# ProPrj_IR-Sensor-I2C_2025-01-15_1.net
KiCad netlist of a schematic drawn in EasyEDA Pro
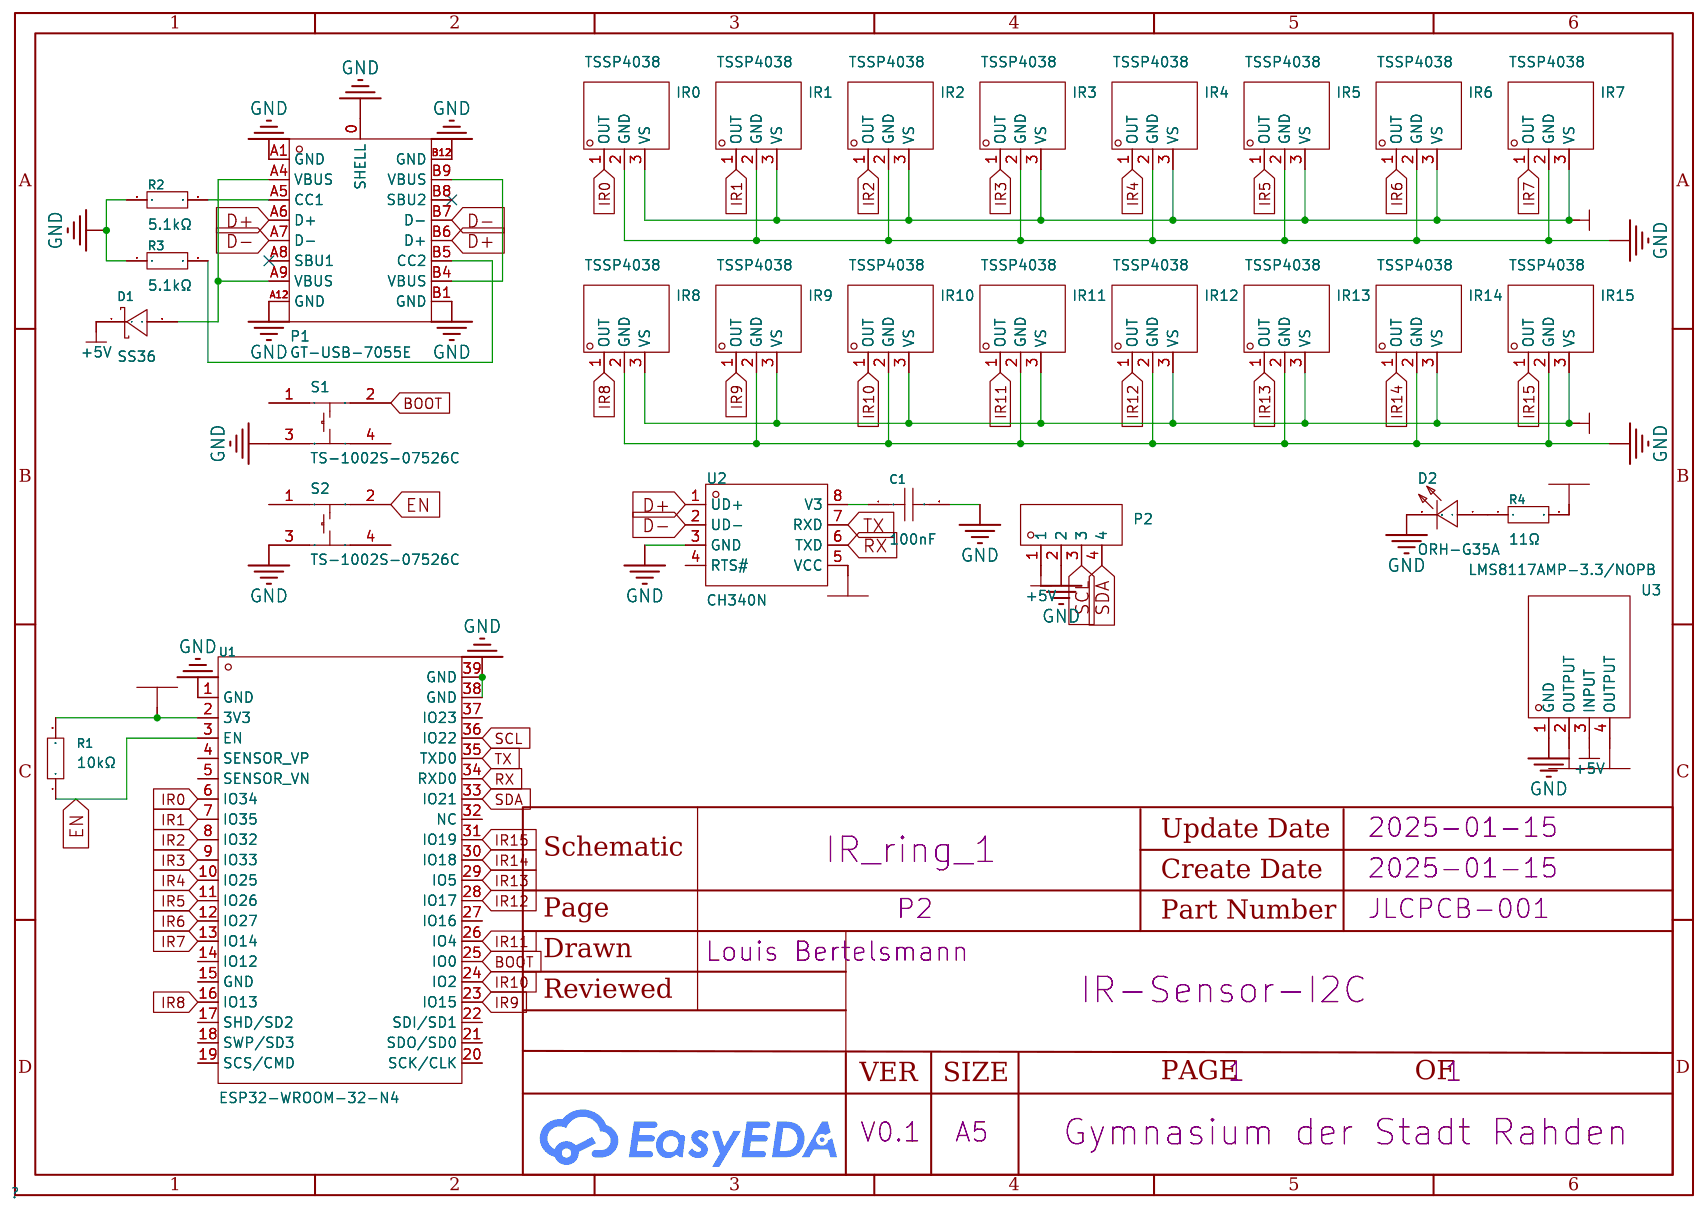
[diagram p0: schematic sheet]

(export (version "E")
  (design (tool "Eeschema 10.0.6"))
  (components
    (comp (ref "C1")
      (value "100nF")
      (footprint "easyedapro:C0603")
      (fields
        (field (name "Manufacturer Part") "CC0603KRX7R9BB104")
        (field (name "Manufacturer") "YAGEO(国巨)")
      )
      (libsource (lib "easyedapro") (part "CC0603KRX7R9BB104"))
    )
    (comp (ref "D1")
      (value "SS36")
      (footprint "easyedapro:SMA_L4.4-W2.8-LS5.4-RD")
      (description "Forward Voltage (Vf@If):700mV@3A Reverse Voltage (Vr):60V Average Rectified Current (Io):3A")
      (fields (field (name "Manufacturer") "晶导微电子"))
      (libsource (lib "easyedapro") (part "SS36_C116712"))
    )
    (comp (ref "D2")
      (value "ORH-G35A")
      (footprint "easyedapro:LED0805-R-RD")
      (fields (field (name "Manufacturer") "Orient(奥伦德)"))
      (libsource (lib "easyedapro") (part "ORH-G35A"))
    )
    (comp (ref "IR0")
      (value "TSSP4038")
      (footprint "easyedapro:SENSOR-TH_TSSP40X")
      (fields (field (name "Manufacturer") "VISHAY(威世)"))
      (libsource (lib "easyedapro") (part "TSSP4038"))
    )
    (comp (ref "IR1")
      (value "TSSP4038")
      (footprint "easyedapro:SENSOR-TH_TSSP40X")
      (fields (field (name "Manufacturer") "VISHAY(威世)"))
      (libsource (lib "easyedapro") (part "TSSP4038"))
    )
    (comp (ref "IR2")
      (value "TSSP4038")
      (footprint "easyedapro:SENSOR-TH_TSSP40X")
      (fields (field (name "Manufacturer") "VISHAY(威世)"))
      (libsource (lib "easyedapro") (part "TSSP4038"))
    )
    (comp (ref "IR3")
      (value "TSSP4038")
      (footprint "easyedapro:SENSOR-TH_TSSP40X")
      (fields (field (name "Manufacturer") "VISHAY(威世)"))
      (libsource (lib "easyedapro") (part "TSSP4038"))
    )
    (comp (ref "IR4")
      (value "TSSP4038")
      (footprint "easyedapro:SENSOR-TH_TSSP40X")
      (fields (field (name "Manufacturer") "VISHAY(威世)"))
      (libsource (lib "easyedapro") (part "TSSP4038"))
    )
    (comp (ref "IR5")
      (value "TSSP4038")
      (footprint "easyedapro:SENSOR-TH_TSSP40X")
      (fields (field (name "Manufacturer") "VISHAY(威世)"))
      (libsource (lib "easyedapro") (part "TSSP4038"))
    )
    (comp (ref "IR6")
      (value "TSSP4038")
      (footprint "easyedapro:SENSOR-TH_TSSP40X")
      (fields (field (name "Manufacturer") "VISHAY(威世)"))
      (libsource (lib "easyedapro") (part "TSSP4038"))
    )
    (comp (ref "IR7")
      (value "TSSP4038")
      (footprint "easyedapro:SENSOR-TH_TSSP40X")
      (fields (field (name "Manufacturer") "VISHAY(威世)"))
      (libsource (lib "easyedapro") (part "TSSP4038"))
    )
    (comp (ref "IR8")
      (value "TSSP4038")
      (footprint "easyedapro:SENSOR-TH_TSSP40X")
      (fields (field (name "Manufacturer") "VISHAY(威世)"))
      (libsource (lib "easyedapro") (part "TSSP4038"))
    )
    (comp (ref "IR9")
      (value "TSSP4038")
      (footprint "easyedapro:SENSOR-TH_TSSP40X")
      (fields (field (name "Manufacturer") "VISHAY(威世)"))
      (libsource (lib "easyedapro") (part "TSSP4038"))
    )
    (comp (ref "IR10")
      (value "TSSP4038")
      (footprint "easyedapro:SENSOR-TH_TSSP40X")
      (fields (field (name "Manufacturer") "VISHAY(威世)"))
      (libsource (lib "easyedapro") (part "TSSP4038"))
    )
    (comp (ref "IR11")
      (value "TSSP4038")
      (footprint "easyedapro:SENSOR-TH_TSSP40X")
      (fields (field (name "Manufacturer") "VISHAY(威世)"))
      (libsource (lib "easyedapro") (part "TSSP4038"))
    )
    (comp (ref "IR12")
      (value "TSSP4038")
      (footprint "easyedapro:SENSOR-TH_TSSP40X")
      (fields (field (name "Manufacturer") "VISHAY(威世)"))
      (libsource (lib "easyedapro") (part "TSSP4038"))
    )
    (comp (ref "IR13")
      (value "TSSP4038")
      (footprint "easyedapro:SENSOR-TH_TSSP40X")
      (fields (field (name "Manufacturer") "VISHAY(威世)"))
      (libsource (lib "easyedapro") (part "TSSP4038"))
    )
    (comp (ref "IR14")
      (value "TSSP4038")
      (footprint "easyedapro:SENSOR-TH_TSSP40X")
      (fields (field (name "Manufacturer") "VISHAY(威世)"))
      (libsource (lib "easyedapro") (part "TSSP4038"))
    )
    (comp (ref "IR15")
      (value "TSSP4038")
      (footprint "easyedapro:SENSOR-TH_TSSP40X")
      (fields (field (name "Manufacturer") "VISHAY(威世)"))
      (libsource (lib "easyedapro") (part "TSSP4038"))
    )
    (comp (ref "P1")
      (value "GT-USB-7055E")
      (footprint "easyedapro:USB-C-SMD_GT-USB-7055E")
      (fields (field (name "Manufacturer") "G-Switch(品赞)"))
      (libsource (lib "easyedapro") (part "GT-USB-7055E"))
    )
    (comp (ref "P2")
      (value "DZ254S-11-04-48")
      (footprint "easyedapro:HDR-SMD_4P-P2.54-V-M-LS4.8_R2")
      (fields (field (name "Manufacturer") "DEALON(德艺隆)"))
      (libsource (lib "easyedapro") (part "DZ254S-11-04-48"))
    )
    (comp (ref "R1")
      (value "10kΩ")
      (footprint "easyedapro:R0603")
      (fields
        (field (name "Manufacturer Part") "0603WAF1002T5E")
        (field (name "Manufacturer") "UNI-ROYAL(厚声)")
      )
      (libsource (lib "easyedapro") (part "0603WAF1002T5E"))
    )
    (comp (ref "R2")
      (value "5.1kΩ")
      (footprint "easyedapro:R0603")
      (fields
        (field (name "Manufacturer Part") "0603WAF5101T5E")
        (field (name "Manufacturer") "UNI-ROYAL(厚声)")
      )
      (libsource (lib "easyedapro") (part "0603WAF5101T5E"))
    )
    (comp (ref "R3")
      (value "5.1kΩ")
      (footprint "easyedapro:R0603")
      (fields
        (field (name "Manufacturer Part") "0603WAF5101T5E")
        (field (name "Manufacturer") "UNI-ROYAL(厚声)")
      )
      (libsource (lib "easyedapro") (part "0603WAF5101T5E"))
    )
    (comp (ref "R4")
      (value "11Ω")
      (footprint "easyedapro:R0603")
      (fields
        (field (name "Manufacturer Part") "0603WAF110JT5E")
        (field (name "Manufacturer") "UNI-ROYAL(厚声)")
      )
      (libsource (lib "easyedapro") (part "0603WAF110JT5E"))
    )
    (comp (ref "S1")
      (value "TS-1002S-07526C")
      (footprint "easyedapro:SW-SMD_4P-L6.0-W6.0-P4.50-LS9.0-2")
      (fields (field (name "Manufacturer") "XUNPU(讯普)"))
      (libsource (lib "easyedapro") (part "TS-1002S-07526C"))
    )
    (comp (ref "S2")
      (value "TS-1002S-07526C")
      (footprint "easyedapro:SW-SMD_4P-L6.0-W6.0-P4.50-LS9.0-2")
      (fields (field (name "Manufacturer") "XUNPU(讯普)"))
      (libsource (lib "easyedapro") (part "TS-1002S-07526C"))
    )
    (comp (ref "U1")
      (value "ESP32-WROOM-32-N4")
      (footprint "easyedapro:WIFIM-SMD_ESP32-WROOM-32-N4")
      (fields (field (name "Manufacturer") "ESPRESSIF(乐鑫)"))
      (libsource (lib "easyedapro") (part "ESP32-WROOM-32"))
    )
    (comp (ref "U2")
      (value "CH340N")
      (footprint "easyedapro:SOP-8_L4.9-W3.9-P1.27-LS6.0-BL")
      (fields (field (name "Manufacturer") "WCH(南京沁恒)"))
      (libsource (lib "easyedapro") (part "CH340N_C2977777"))
    )
    (comp (ref "U3")
      (value "LMS8117AMP-3.3/NOPB")
      (footprint "easyedapro:SOT-223_L6.5-W3.5-P2.30-LS7.0-BR")
      (fields (field (name "Manufacturer") "TI(德州仪器)"))
      (libsource (lib "easyedapro") (part "LMS8117AMP-3.3/NOPB"))
    )
  )
  (nets
    (net (code "1") (name "+5V") (class "Default")
      (node (ref "D1") (pin "1") (pinfunction "K_1") (pintype "input"))
      (node (ref "P2") (pin "1") (pinfunction "1_1") (pintype "unspecified"))
      (node (ref "U3") (pin "3") (pinfunction "INPUT_3") (pintype "unspecified"))
    )
    (net (code "2") (name "3V3") (class "Default")
      (node (ref "IR0") (pin "3") (pinfunction "VS_3") (pintype "input"))
      (node (ref "IR1") (pin "3") (pinfunction "VS_3") (pintype "input"))
      (node (ref "IR10") (pin "3") (pinfunction "VS_3") (pintype "input"))
      (node (ref "IR11") (pin "3") (pinfunction "VS_3") (pintype "input"))
      (node (ref "IR12") (pin "3") (pinfunction "VS_3") (pintype "input"))
      (node (ref "IR13") (pin "3") (pinfunction "VS_3") (pintype "input"))
      (node (ref "IR14") (pin "3") (pinfunction "VS_3") (pintype "input"))
      (node (ref "IR15") (pin "3") (pinfunction "VS_3") (pintype "input"))
      (node (ref "IR2") (pin "3") (pinfunction "VS_3") (pintype "input"))
      (node (ref "IR3") (pin "3") (pinfunction "VS_3") (pintype "input"))
      (node (ref "IR4") (pin "3") (pinfunction "VS_3") (pintype "input"))
      (node (ref "IR5") (pin "3") (pinfunction "VS_3") (pintype "input"))
      (node (ref "IR6") (pin "3") (pinfunction "VS_3") (pintype "input"))
      (node (ref "IR7") (pin "3") (pinfunction "VS_3") (pintype "input"))
      (node (ref "IR8") (pin "3") (pinfunction "VS_3") (pintype "input"))
      (node (ref "IR9") (pin "3") (pinfunction "VS_3") (pintype "input"))
      (node (ref "R1") (pin "2") (pinfunction "2_2") (pintype "input"))
      (node (ref "R4") (pin "2") (pinfunction "2_2") (pintype "input"))
      (node (ref "U1") (pin "2") (pinfunction "3V3_2") (pintype "input"))
      (node (ref "U2") (pin "5") (pinfunction "VCC_5") (pintype "unspecified"))
      (node (ref "U3") (pin "2") (pinfunction "OUTPUT_2") (pintype "unspecified"))
      (node (ref "U3") (pin "4") (pinfunction "OUTPUT_4") (pintype "unspecified"))
    )
    (net (code "3") (name "BOOT") (class "Default")
      (node (ref "S1") (pin "2") (pinfunction "2_2") (pintype "input"))
      (node (ref "U1") (pin "25") (pinfunction "IO0_25") (pintype "input"))
    )
    (net (code "4") (name "D+") (class "Default")
      (node (ref "P1") (pin "A6") (pinfunction "D+_A6") (pintype "unspecified"))
      (node (ref "P1") (pin "B6") (pinfunction "D+_B6") (pintype "unspecified"))
      (node (ref "U2") (pin "1") (pinfunction "UD+_1") (pintype "unspecified"))
    )
    (net (code "5") (name "D-") (class "Default")
      (node (ref "P1") (pin "A7") (pinfunction "D-_A7") (pintype "unspecified"))
      (node (ref "P1") (pin "B7") (pinfunction "D-_B7") (pintype "unspecified"))
      (node (ref "U2") (pin "2") (pinfunction "UD-_2") (pintype "unspecified"))
    )
    (net (code "6") (name "EN") (class "Default")
      (node (ref "R1") (pin "1") (pinfunction "1_1") (pintype "input"))
      (node (ref "S2") (pin "2") (pinfunction "2_2") (pintype "input"))
      (node (ref "U1") (pin "3") (pinfunction "EN_3") (pintype "input"))
    )
    (net (code "7") (name "GND") (class "Default")
      (node (ref "C1") (pin "2") (pinfunction "2_2") (pintype "input"))
      (node (ref "D2") (pin "2") (pinfunction "C_2") (pintype "unspecified"))
      (node (ref "IR0") (pin "2") (pinfunction "GND_2") (pintype "input"))
      (node (ref "IR1") (pin "2") (pinfunction "GND_2") (pintype "input"))
      (node (ref "IR10") (pin "2") (pinfunction "GND_2") (pintype "input"))
      (node (ref "IR11") (pin "2") (pinfunction "GND_2") (pintype "input"))
      (node (ref "IR12") (pin "2") (pinfunction "GND_2") (pintype "input"))
      (node (ref "IR13") (pin "2") (pinfunction "GND_2") (pintype "input"))
      (node (ref "IR14") (pin "2") (pinfunction "GND_2") (pintype "input"))
      (node (ref "IR15") (pin "2") (pinfunction "GND_2") (pintype "input"))
      (node (ref "IR2") (pin "2") (pinfunction "GND_2") (pintype "input"))
      (node (ref "IR3") (pin "2") (pinfunction "GND_2") (pintype "input"))
      (node (ref "IR4") (pin "2") (pinfunction "GND_2") (pintype "input"))
      (node (ref "IR5") (pin "2") (pinfunction "GND_2") (pintype "input"))
      (node (ref "IR6") (pin "2") (pinfunction "GND_2") (pintype "input"))
      (node (ref "IR7") (pin "2") (pinfunction "GND_2") (pintype "input"))
      (node (ref "IR8") (pin "2") (pinfunction "GND_2") (pintype "input"))
      (node (ref "IR9") (pin "2") (pinfunction "GND_2") (pintype "input"))
      (node (ref "P1") (pin "0") (pinfunction "SHELL_0") (pintype "unspecified"))
      (node (ref "P1") (pin "A1") (pinfunction "GND_A1") (pintype "unspecified"))
      (node (ref "P1") (pin "A12") (pinfunction "GND_A12") (pintype "unspecified"))
      (node (ref "P1") (pin "B1") (pinfunction "GND_B1") (pintype "unspecified"))
      (node (ref "P1") (pin "B12") (pinfunction "GND_B12") (pintype "unspecified"))
      (node (ref "P2") (pin "2") (pinfunction "2_2") (pintype "unspecified"))
      (node (ref "R2") (pin "1") (pinfunction "1_1") (pintype "input"))
      (node (ref "R3") (pin "1") (pinfunction "1_1") (pintype "input"))
      (node (ref "S1") (pin "3") (pinfunction "3_3") (pintype "input"))
      (node (ref "S2") (pin "3") (pinfunction "3_3") (pintype "input"))
      (node (ref "U1") (pin "1") (pinfunction "GND_1") (pintype "input"))
      (node (ref "U1") (pin "38") (pinfunction "GND_38") (pintype "input"))
      (node (ref "U1") (pin "39") (pinfunction "GND_39") (pintype "input"))
      (node (ref "U2") (pin "3") (pinfunction "GND_3") (pintype "unspecified"))
      (node (ref "U3") (pin "1") (pinfunction "GND_1") (pintype "unspecified"))
    )
    (net (code "8") (name "IR0") (class "Default")
      (node (ref "IR0") (pin "1") (pinfunction "OUT_1") (pintype "input"))
      (node (ref "U1") (pin "6") (pinfunction "IO34_6") (pintype "input"))
    )
    (net (code "9") (name "IR1") (class "Default")
      (node (ref "IR1") (pin "1") (pinfunction "OUT_1") (pintype "input"))
      (node (ref "U1") (pin "7") (pinfunction "IO35_7") (pintype "input"))
    )
    (net (code "10") (name "IR2") (class "Default")
      (node (ref "IR2") (pin "1") (pinfunction "OUT_1") (pintype "input"))
      (node (ref "U1") (pin "8") (pinfunction "IO32_8") (pintype "input"))
    )
    (net (code "11") (name "IR3") (class "Default")
      (node (ref "IR3") (pin "1") (pinfunction "OUT_1") (pintype "input"))
      (node (ref "U1") (pin "9") (pinfunction "IO33_9") (pintype "input"))
    )
    (net (code "12") (name "IR4") (class "Default")
      (node (ref "IR4") (pin "1") (pinfunction "OUT_1") (pintype "input"))
      (node (ref "U1") (pin "10") (pinfunction "IO25_10") (pintype "input"))
    )
    (net (code "13") (name "IR5") (class "Default")
      (node (ref "IR5") (pin "1") (pinfunction "OUT_1") (pintype "input"))
      (node (ref "U1") (pin "11") (pinfunction "IO26_11") (pintype "input"))
    )
    (net (code "14") (name "IR6") (class "Default")
      (node (ref "IR6") (pin "1") (pinfunction "OUT_1") (pintype "input"))
      (node (ref "U1") (pin "12") (pinfunction "IO27_12") (pintype "input"))
    )
    (net (code "15") (name "IR7") (class "Default")
      (node (ref "IR7") (pin "1") (pinfunction "OUT_1") (pintype "input"))
      (node (ref "U1") (pin "13") (pinfunction "IO14_13") (pintype "input"))
    )
    (net (code "16") (name "IR8") (class "Default")
      (node (ref "IR8") (pin "1") (pinfunction "OUT_1") (pintype "input"))
      (node (ref "U1") (pin "16") (pinfunction "IO13_16") (pintype "input"))
    )
    (net (code "17") (name "IR9") (class "Default")
      (node (ref "IR9") (pin "1") (pinfunction "OUT_1") (pintype "input"))
      (node (ref "U1") (pin "23") (pinfunction "IO15_23") (pintype "input"))
    )
    (net (code "18") (name "IR10") (class "Default")
      (node (ref "IR10") (pin "1") (pinfunction "OUT_1") (pintype "input"))
      (node (ref "U1") (pin "24") (pinfunction "IO2_24") (pintype "input"))
    )
    (net (code "19") (name "IR11") (class "Default")
      (node (ref "IR11") (pin "1") (pinfunction "OUT_1") (pintype "input"))
      (node (ref "U1") (pin "26") (pinfunction "IO4_26") (pintype "input"))
    )
    (net (code "20") (name "IR12") (class "Default")
      (node (ref "IR12") (pin "1") (pinfunction "OUT_1") (pintype "input"))
      (node (ref "U1") (pin "28") (pinfunction "IO17_28") (pintype "input"))
    )
    (net (code "21") (name "IR13") (class "Default")
      (node (ref "IR13") (pin "1") (pinfunction "OUT_1") (pintype "input"))
      (node (ref "U1") (pin "29") (pinfunction "IO5_29") (pintype "input"))
    )
    (net (code "22") (name "IR14") (class "Default")
      (node (ref "IR14") (pin "1") (pinfunction "OUT_1") (pintype "input"))
      (node (ref "U1") (pin "30") (pinfunction "IO18_30") (pintype "input"))
    )
    (net (code "23") (name "IR15") (class "Default")
      (node (ref "IR15") (pin "1") (pinfunction "OUT_1") (pintype "input"))
      (node (ref "U1") (pin "31") (pinfunction "IO19_31") (pintype "input"))
    )
    (net (code "24") (name "Net-(D1-A)") (class "Default")
      (node (ref "D1") (pin "2") (pinfunction "A_2") (pintype "input"))
      (node (ref "P1") (pin "A4") (pinfunction "VBUS_A4") (pintype "unspecified"))
      (node (ref "P1") (pin "A9") (pinfunction "VBUS_A9") (pintype "unspecified"))
    )
    (net (code "25") (name "Net-(D2-A)") (class "Default")
      (node (ref "D2") (pin "1") (pinfunction "A_1") (pintype "unspecified"))
      (node (ref "R4") (pin "1") (pinfunction "1_1") (pintype "input"))
    )
    (net (code "26") (name "Net-(P1-CC1)") (class "Default")
      (node (ref "P1") (pin "A5") (pinfunction "CC1_A5") (pintype "unspecified"))
      (node (ref "R2") (pin "2") (pinfunction "2_2") (pintype "input"))
    )
    (net (code "27") (name "Net-(P1-CC2)") (class "Default")
      (node (ref "P1") (pin "B5") (pinfunction "CC2_B5") (pintype "unspecified"))
      (node (ref "R3") (pin "2") (pinfunction "2_2") (pintype "input"))
    )
    (net (code "28") (name "Net-(P1-VBUS-PadB4)") (class "Default")
      (node (ref "P1") (pin "B4") (pinfunction "VBUS_B4") (pintype "unspecified"))
      (node (ref "P1") (pin "B9") (pinfunction "VBUS_B9") (pintype "unspecified"))
    )
    (net (code "29") (name "Net-(U2-V3)") (class "Default")
      (node (ref "C1") (pin "1") (pinfunction "1_1") (pintype "input"))
      (node (ref "U2") (pin "8") (pinfunction "V3_8") (pintype "unspecified"))
    )
    (net (code "30") (name "RX") (class "Default")
      (node (ref "U1") (pin "34") (pinfunction "RXD0_34") (pintype "input"))
      (node (ref "U2") (pin "6") (pinfunction "TXD_6") (pintype "unspecified"))
    )
    (net (code "31") (name "SCL") (class "Default")
      (node (ref "P2") (pin "3") (pinfunction "3_3") (pintype "unspecified"))
      (node (ref "U1") (pin "36") (pinfunction "IO22_36") (pintype "input"))
    )
    (net (code "32") (name "SDA") (class "Default")
      (node (ref "P2") (pin "4") (pinfunction "4_4") (pintype "unspecified"))
      (node (ref "U1") (pin "33") (pinfunction "IO21_33") (pintype "input"))
    )
    (net (code "33") (name "TX") (class "Default")
      (node (ref "U1") (pin "35") (pinfunction "TXD0_35") (pintype "input"))
      (node (ref "U2") (pin "7") (pinfunction "RXD_7") (pintype "unspecified"))
    )
    (net (code "34") (name "unconnected-(P1-SBU1-PadA8)") (class "Default")
      (node (ref "P1") (pin "A8") (pinfunction "SBU1_A8") (pintype "unspecified+no_connect"))
    )
    (net (code "35") (name "unconnected-(P1-SBU2-PadB8)") (class "Default")
      (node (ref "P1") (pin "B8") (pinfunction "SBU2_B8") (pintype "unspecified+no_connect"))
    )
    (net (code "36") (name "unconnected-(S1-Pad1)") (class "Default")
      (node (ref "S1") (pin "1") (pinfunction "1_1") (pintype "input"))
    )
    (net (code "37") (name "unconnected-(S1-Pad4)") (class "Default")
      (node (ref "S1") (pin "4") (pinfunction "4_4") (pintype "input"))
    )
    (net (code "38") (name "unconnected-(S2-Pad1)") (class "Default")
      (node (ref "S2") (pin "1") (pinfunction "1_1") (pintype "input"))
    )
    (net (code "39") (name "unconnected-(S2-Pad4)") (class "Default")
      (node (ref "S2") (pin "4") (pinfunction "4_4") (pintype "input"))
    )
    (net (code "40") (name "unconnected-(U1-GND-Pad15)") (class "Default")
      (node (ref "U1") (pin "15") (pinfunction "GND_15") (pintype "input"))
    )
    (net (code "41") (name "unconnected-(U1-IO12-Pad14)") (class "Default")
      (node (ref "U1") (pin "14") (pinfunction "IO12_14") (pintype "input"))
    )
    (net (code "42") (name "unconnected-(U1-IO16-Pad27)") (class "Default")
      (node (ref "U1") (pin "27") (pinfunction "IO16_27") (pintype "input"))
    )
    (net (code "43") (name "unconnected-(U1-IO23-Pad37)") (class "Default")
      (node (ref "U1") (pin "37") (pinfunction "IO23_37") (pintype "input"))
    )
    (net (code "44") (name "unconnected-(U1-NC-Pad32)") (class "Default")
      (node (ref "U1") (pin "32") (pinfunction "NC_32") (pintype "input"))
    )
    (net (code "45") (name "unconnected-(U1-SCK{slash}CLK-Pad20)") (class "Default")
      (node (ref "U1") (pin "20") (pinfunction "SCK/CLK_20") (pintype "input"))
    )
    (net (code "46") (name "unconnected-(U1-SCS{slash}CMD-Pad19)") (class "Default")
      (node (ref "U1") (pin "19") (pinfunction "SCS/CMD_19") (pintype "input"))
    )
    (net (code "47") (name "unconnected-(U1-SDI{slash}SD1-Pad22)") (class "Default")
      (node (ref "U1") (pin "22") (pinfunction "SDI/SD1_22") (pintype "input"))
    )
    (net (code "48") (name "unconnected-(U1-SDO{slash}SD0-Pad21)") (class "Default")
      (node (ref "U1") (pin "21") (pinfunction "SDO/SD0_21") (pintype "input"))
    )
    (net (code "49") (name "unconnected-(U1-SENSOR_VN-Pad5)") (class "Default")
      (node (ref "U1") (pin "5") (pinfunction "SENSOR_VN_5") (pintype "input"))
    )
    (net (code "50") (name "unconnected-(U1-SENSOR_VP-Pad4)") (class "Default")
      (node (ref "U1") (pin "4") (pinfunction "SENSOR_VP_4") (pintype "input"))
    )
    (net (code "51") (name "unconnected-(U1-SHD{slash}SD2-Pad17)") (class "Default")
      (node (ref "U1") (pin "17") (pinfunction "SHD/SD2_17") (pintype "input"))
    )
    (net (code "52") (name "unconnected-(U1-SWP{slash}SD3-Pad18)") (class "Default")
      (node (ref "U1") (pin "18") (pinfunction "SWP/SD3_18") (pintype "input"))
    )
    (net (code "53") (name "unconnected-(U2-RTS#-Pad4)") (class "Default")
      (node (ref "U2") (pin "4") (pinfunction "RTS#_4") (pintype "unspecified"))
    )
  )
)
